# SOL_zSat_camera.net
KiCad netlist of a schematic drawn in EAGLE
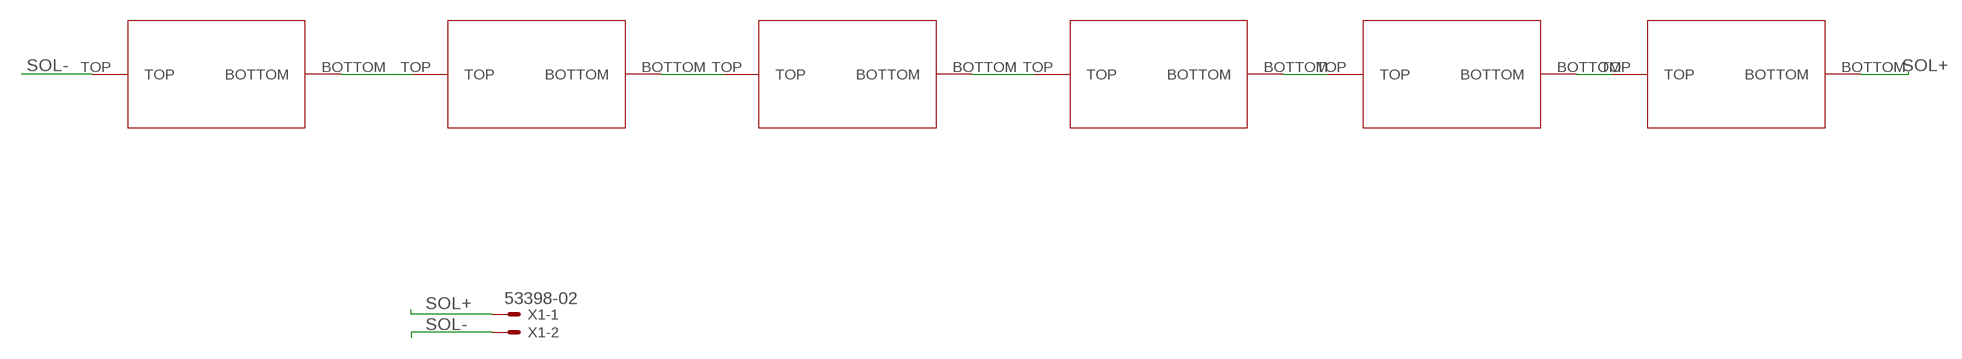
[diagram p0: schematic, sheet 1]

(export (version "E")
  (design (tool "Eeschema 10.0.6"))
  (components
    (comp (ref "U$1")
      (value "SOL_26X52")
      (footprint "eagle-import:SOLAR_52X26")
      (libsource (lib "eagle-import") (part "SOL_26X52"))
    )
    (comp (ref "U$2")
      (value "SOL_26X52")
      (footprint "eagle-import:SOLAR_52X26")
      (libsource (lib "eagle-import") (part "SOL_26X52"))
    )
    (comp (ref "U$3")
      (value "SOL_26X52")
      (footprint "eagle-import:SOLAR_52X26")
      (libsource (lib "eagle-import") (part "SOL_26X52"))
    )
    (comp (ref "U$4")
      (value "SOL_26X52")
      (footprint "eagle-import:SOLAR_52X26")
      (libsource (lib "eagle-import") (part "SOL_26X52"))
    )
    (comp (ref "U$5")
      (value "SOL_26X52")
      (footprint "eagle-import:SOLAR_52X26")
      (libsource (lib "eagle-import") (part "SOL_26X52"))
    )
    (comp (ref "U$6")
      (value "SOL_26X52")
      (footprint "eagle-import:SOLAR_52X26")
      (libsource (lib "eagle-import") (part "SOL_26X52"))
    )
    (comp (ref "X1")
      (value "53398-02")
      (footprint "eagle-import:53398-02")
      (fields (field (name "MF") "MOLEX"))
      (libsource (lib "eagle-import") (part "53?-02398"))
    )
  )
  (nets
    (net (code "1") (name "/SOL+") (class "Default")
      (node (ref "U$6") (pin "BOTTOM") (pinfunction "BOTTOM_BOTTOM") (pintype "bidirectional"))
      (node (ref "X1") (pin "1") (pinfunction "S_1") (pintype "passive"))
    )
    (net (code "2") (name "/SOL-") (class "Default")
      (node (ref "U$1") (pin "TOP") (pinfunction "TOP_TOP") (pintype "bidirectional"))
      (node (ref "X1") (pin "2") (pinfunction "S_2") (pintype "passive"))
    )
    (net (code "3") (name "Net-(U$1-PadBOTTOM)") (class "Default")
      (node (ref "U$1") (pin "BOTTOM") (pinfunction "BOTTOM_BOTTOM") (pintype "bidirectional"))
      (node (ref "U$2") (pin "TOP") (pinfunction "TOP_TOP") (pintype "bidirectional"))
    )
    (net (code "4") (name "Net-(U$2-PadBOTTOM)") (class "Default")
      (node (ref "U$2") (pin "BOTTOM") (pinfunction "BOTTOM_BOTTOM") (pintype "bidirectional"))
      (node (ref "U$3") (pin "TOP") (pinfunction "TOP_TOP") (pintype "bidirectional"))
    )
    (net (code "5") (name "Net-(U$3-PadBOTTOM)") (class "Default")
      (node (ref "U$3") (pin "BOTTOM") (pinfunction "BOTTOM_BOTTOM") (pintype "bidirectional"))
      (node (ref "U$4") (pin "TOP") (pinfunction "TOP_TOP") (pintype "bidirectional"))
    )
    (net (code "6") (name "Net-(U$4-PadBOTTOM)") (class "Default")
      (node (ref "U$4") (pin "BOTTOM") (pinfunction "BOTTOM_BOTTOM") (pintype "bidirectional"))
      (node (ref "U$5") (pin "TOP") (pinfunction "TOP_TOP") (pintype "bidirectional"))
    )
    (net (code "7") (name "Net-(U$5-PadBOTTOM)") (class "Default")
      (node (ref "U$5") (pin "BOTTOM") (pinfunction "BOTTOM_BOTTOM") (pintype "bidirectional"))
      (node (ref "U$6") (pin "TOP") (pinfunction "TOP_TOP") (pintype "bidirectional"))
    )
  )
)
